# Light_Controller.net
KiCad netlist of a schematic drawn in EAGLE
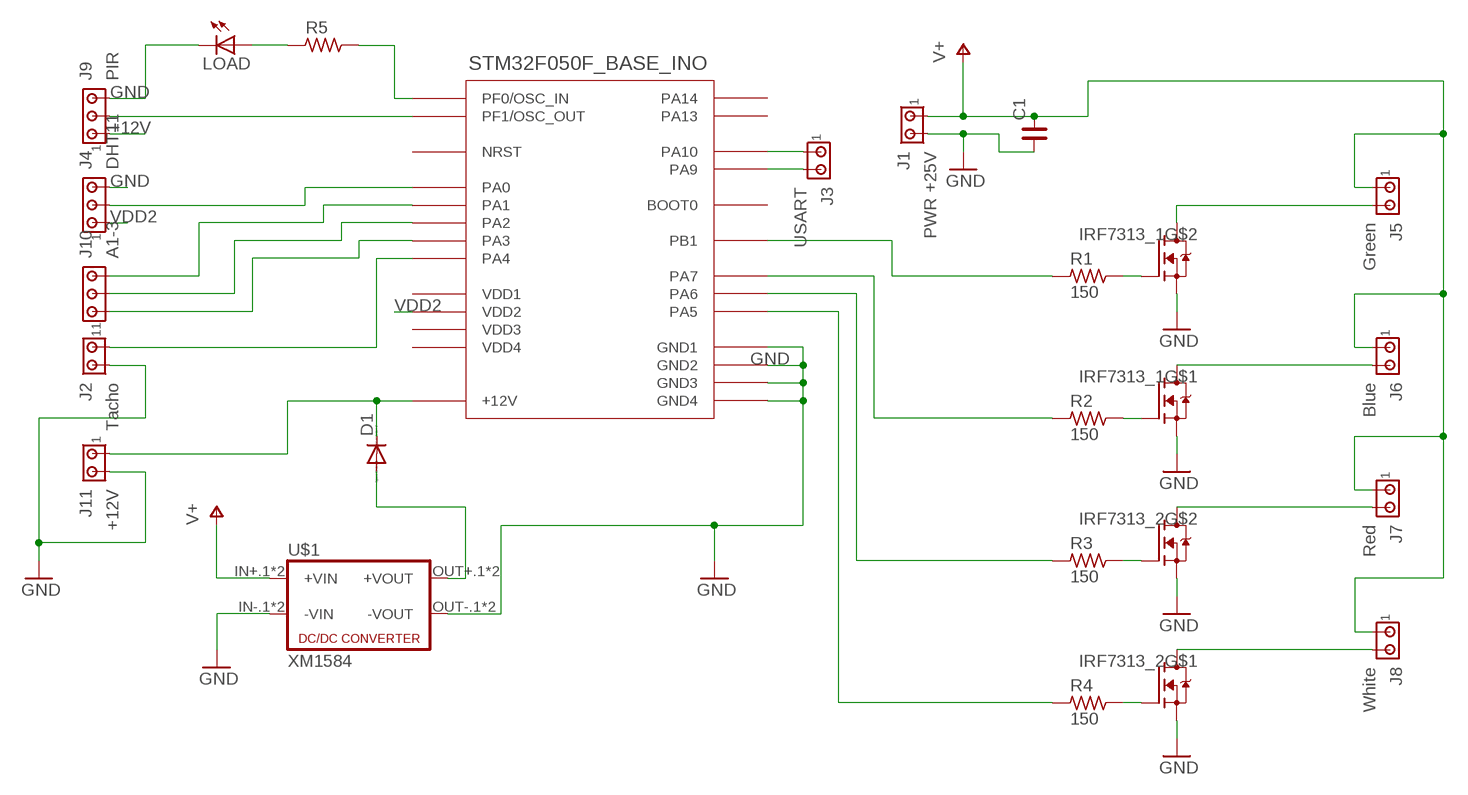
[diagram p0: schematic, sheet 1]

(export (version "E")
  (design (tool "Eeschema 10.0.6"))
  (components
    (comp (ref "C1")
      (value "C_0603")
      (footprint "eagle-import:C0603")
      (libsource (lib "eagle-import") (part "C_0603"))
    )
    (comp (ref "D1")
      (value "DIODE-DO214AC")
      (footprint "eagle-import:DO214AC")
      (libsource (lib "eagle-import") (part "DIODE-DO214AC"))
    )
    (comp (ref "IRF7313_1")
      (value "IRF7313")
      (footprint "eagle-import:SO-8")
      (libsource (lib "eagle-import") (part "IRF7313"))
    )
    (comp (ref "IRF7313_2")
      (value "IRF7313")
      (footprint "eagle-import:SO-8")
      (libsource (lib "eagle-import") (part "IRF7313"))
    )
    (comp (ref "J1")
      (value "PWR +25V")
      (footprint "eagle-import:10X02MTA")
      (libsource (lib "eagle-import") (part "MTA02-100"))
    )
    (comp (ref "J2")
      (value "Tacho")
      (footprint "eagle-import:10X02MTA")
      (libsource (lib "eagle-import") (part "MTA02-100"))
    )
    (comp (ref "J3")
      (value "USART")
      (footprint "eagle-import:10X02MTA")
      (libsource (lib "eagle-import") (part "MTA02-100"))
    )
    (comp (ref "J4")
      (value "DHT11")
      (footprint "eagle-import:10X03MTA")
      (libsource (lib "eagle-import") (part "MTA03-100"))
    )
    (comp (ref "J5")
      (value "Green")
      (footprint "eagle-import:10X02MTA")
      (libsource (lib "eagle-import") (part "MTA02-100"))
    )
    (comp (ref "J6")
      (value "Blue")
      (footprint "eagle-import:10X02MTA")
      (libsource (lib "eagle-import") (part "MTA02-100"))
    )
    (comp (ref "J7")
      (value "Red")
      (footprint "eagle-import:10X02MTA")
      (libsource (lib "eagle-import") (part "MTA02-100"))
    )
    (comp (ref "J8")
      (value "White")
      (footprint "eagle-import:10X02MTA")
      (libsource (lib "eagle-import") (part "MTA02-100"))
    )
    (comp (ref "J9")
      (value "PIR")
      (footprint "eagle-import:10X03MTA")
      (libsource (lib "eagle-import") (part "MTA03-100"))
    )
    (comp (ref "J10")
      (value "A1-3")
      (footprint "eagle-import:10X03MTA")
      (libsource (lib "eagle-import") (part "MTA03-100"))
    )
    (comp (ref "J11")
      (value "+12V")
      (footprint "eagle-import:10X02MTA")
      (libsource (lib "eagle-import") (part "MTA02-100"))
    )
    (comp (ref "LOAD")
      (value "LEDCHIPLED_1206")
      (footprint "eagle-import:CHIPLED_1206")
      (libsource (lib "eagle-import") (part "LEDCHIPLED_1206"))
    )
    (comp (ref "R1")
      (value "150")
      (footprint "eagle-import:R1206")
      (libsource (lib "eagle-import") (part "R_1206"))
    )
    (comp (ref "R2")
      (value "150")
      (footprint "eagle-import:R1206")
      (libsource (lib "eagle-import") (part "R_1206"))
    )
    (comp (ref "R3")
      (value "150")
      (footprint "eagle-import:R1206")
      (libsource (lib "eagle-import") (part "R_1206"))
    )
    (comp (ref "R4")
      (value "150")
      (footprint "eagle-import:R1206")
      (libsource (lib "eagle-import") (part "R_1206"))
    )
    (comp (ref "R5")
      (value "R_1206")
      (footprint "eagle-import:R1206")
      (libsource (lib "eagle-import") (part "R_1206"))
    )
    (comp (ref "STM321")
      (value "STM32F050F_BASE_INO")
      (footprint "eagle-import:STM32_BASE_INO")
      (libsource (lib "eagle-import") (part "STM32F050F_BASE_INO"))
    )
    (comp (ref "U$1")
      (value "XM1584")
      (footprint "eagle-import:XM1584")
      (libsource (lib "eagle-import") (part "XM1584"))
    )
  )
  (nets
    (net (code "1") (name "/+12V") (class "Default")
      (node (ref "D1") (pin "C") (pinfunction "C_C") (pintype "passive"))
      (node (ref "J11") (pin "1") (pinfunction "1_1") (pintype "passive"))
      (node (ref "J9") (pin "1") (pinfunction "1_1") (pintype "passive"))
      (node (ref "STM321") (pin "+12V") (pinfunction "+12V_+12V") (pintype "passive"))
    )
    (net (code "2") (name "/VDD2") (class "Default")
      (node (ref "J4") (pin "1") (pinfunction "1_1") (pintype "passive"))
      (node (ref "STM321") (pin "VDD2") (pinfunction "VDD2_VDD2") (pintype "passive"))
    )
    (net (code "3") (name "GND") (class "Default")
      (node (ref "C1") (pin "1") (pinfunction "1_1") (pintype "passive"))
      (node (ref "IRF7313_1") (pin "1") (pinfunction "S_1") (pintype "passive"))
      (node (ref "IRF7313_1") (pin "3") (pinfunction "S_3") (pintype "passive"))
      (node (ref "IRF7313_2") (pin "1") (pinfunction "S_1") (pintype "passive"))
      (node (ref "IRF7313_2") (pin "3") (pinfunction "S_3") (pintype "passive"))
      (node (ref "J1") (pin "2") (pinfunction "2_2") (pintype "passive"))
      (node (ref "J11") (pin "2") (pinfunction "2_2") (pintype "passive"))
      (node (ref "J2") (pin "2") (pinfunction "2_2") (pintype "passive"))
      (node (ref "J4") (pin "3") (pinfunction "3_3") (pintype "passive"))
      (node (ref "J9") (pin "3") (pinfunction "3_3") (pintype "passive"))
      (node (ref "LOAD") (pin "C") (pinfunction "C_C") (pintype "passive"))
      (node (ref "STM321") (pin "GND1") (pinfunction "GND1_GND1") (pintype "passive"))
      (node (ref "STM321") (pin "GND2") (pinfunction "GND2_GND2") (pintype "passive"))
      (node (ref "STM321") (pin "GND3") (pinfunction "GND3_GND3") (pintype "passive"))
      (node (ref "STM321") (pin "GND4") (pinfunction "GND4_GND4") (pintype "passive"))
      (node (ref "U$1") (pin "IN-.1") (pinfunction "-VIN_IN-.1") (pintype "passive"))
      (node (ref "U$1") (pin "IN-.2") (pinfunction "-VIN_IN-.2") (pintype "passive"))
      (node (ref "U$1") (pin "OUT-.1") (pinfunction "-VOUT_OUT-.1") (pintype "passive"))
      (node (ref "U$1") (pin "OUT-.2") (pinfunction "-VOUT_OUT-.2") (pintype "passive"))
    )
    (net (code "4") (name "Net-(D1-PadA)") (class "Default")
      (node (ref "D1") (pin "A") (pinfunction "A_A") (pintype "passive"))
      (node (ref "U$1") (pin "OUT+.1") (pinfunction "+VOUT_OUT+.1") (pintype "passive"))
      (node (ref "U$1") (pin "OUT+.2") (pinfunction "+VOUT_OUT+.2") (pintype "passive"))
    )
    (net (code "5") (name "Net-(IRF7313_1A-D-Pad7)") (class "Default")
      (node (ref "IRF7313_1") (pin "7") (pinfunction "D_7") (pintype "passive"))
      (node (ref "IRF7313_1") (pin "8") (pinfunction "D_8") (pintype "passive"))
      (node (ref "J6") (pin "2") (pinfunction "2_2") (pintype "passive"))
    )
    (net (code "6") (name "Net-(IRF7313_1A-G)") (class "Default")
      (node (ref "IRF7313_1") (pin "2") (pinfunction "G_2") (pintype "passive"))
      (node (ref "R2") (pin "2") (pinfunction "2_2") (pintype "passive"))
    )
    (net (code "7") (name "Net-(IRF7313_1B-D-Pad5)") (class "Default")
      (node (ref "IRF7313_1") (pin "5") (pinfunction "D_5") (pintype "passive"))
      (node (ref "IRF7313_1") (pin "6") (pinfunction "D_6") (pintype "passive"))
      (node (ref "J5") (pin "2") (pinfunction "2_2") (pintype "passive"))
    )
    (net (code "8") (name "Net-(IRF7313_1B-G)") (class "Default")
      (node (ref "IRF7313_1") (pin "4") (pinfunction "G_4") (pintype "passive"))
      (node (ref "R1") (pin "2") (pinfunction "2_2") (pintype "passive"))
    )
    (net (code "9") (name "Net-(IRF7313_2A-D-Pad7)") (class "Default")
      (node (ref "IRF7313_2") (pin "7") (pinfunction "D_7") (pintype "passive"))
      (node (ref "IRF7313_2") (pin "8") (pinfunction "D_8") (pintype "passive"))
      (node (ref "J8") (pin "2") (pinfunction "2_2") (pintype "passive"))
    )
    (net (code "10") (name "Net-(IRF7313_2A-G)") (class "Default")
      (node (ref "IRF7313_2") (pin "2") (pinfunction "G_2") (pintype "passive"))
      (node (ref "R4") (pin "2") (pinfunction "2_2") (pintype "passive"))
    )
    (net (code "11") (name "Net-(IRF7313_2B-D-Pad5)") (class "Default")
      (node (ref "IRF7313_2") (pin "5") (pinfunction "D_5") (pintype "passive"))
      (node (ref "IRF7313_2") (pin "6") (pinfunction "D_6") (pintype "passive"))
      (node (ref "J7") (pin "2") (pinfunction "2_2") (pintype "passive"))
    )
    (net (code "12") (name "Net-(IRF7313_2B-G)") (class "Default")
      (node (ref "IRF7313_2") (pin "4") (pinfunction "G_4") (pintype "passive"))
      (node (ref "R3") (pin "2") (pinfunction "2_2") (pintype "passive"))
    )
    (net (code "13") (name "Net-(J2-Pad1)") (class "Default")
      (node (ref "J2") (pin "1") (pinfunction "1_1") (pintype "passive"))
      (node (ref "STM321") (pin "PA4") (pinfunction "PA4_PA4") (pintype "passive"))
    )
    (net (code "14") (name "Net-(J3-Pad1)") (class "Default")
      (node (ref "J3") (pin "1") (pinfunction "1_1") (pintype "passive"))
      (node (ref "STM321") (pin "PA10") (pinfunction "PA10_PA10") (pintype "passive"))
    )
    (net (code "15") (name "Net-(J3-Pad2)") (class "Default")
      (node (ref "J3") (pin "2") (pinfunction "2_2") (pintype "passive"))
      (node (ref "STM321") (pin "PA9") (pinfunction "PA9_PA9") (pintype "passive"))
    )
    (net (code "16") (name "Net-(J4-Pad2)") (class "Default")
      (node (ref "J4") (pin "2") (pinfunction "2_2") (pintype "passive"))
      (node (ref "STM321") (pin "PA0") (pinfunction "PA0_PA0") (pintype "passive"))
    )
    (net (code "17") (name "Net-(J10-Pad1)") (class "Default")
      (node (ref "J10") (pin "1") (pinfunction "1_1") (pintype "passive"))
      (node (ref "STM321") (pin "PA3") (pinfunction "PA3_PA3") (pintype "passive"))
    )
    (net (code "18") (name "Net-(J10-Pad2)") (class "Default")
      (node (ref "J10") (pin "2") (pinfunction "2_2") (pintype "passive"))
      (node (ref "STM321") (pin "PA2") (pinfunction "PA2_PA2") (pintype "passive"))
    )
    (net (code "19") (name "Net-(J10-Pad3)") (class "Default")
      (node (ref "J10") (pin "3") (pinfunction "3_3") (pintype "passive"))
      (node (ref "STM321") (pin "PA1") (pinfunction "PA1_PA1") (pintype "passive"))
    )
    (net (code "20") (name "Net-(LOAD-PadA)") (class "Default")
      (node (ref "LOAD") (pin "A") (pinfunction "A_A") (pintype "passive"))
      (node (ref "R5") (pin "1") (pinfunction "1_1") (pintype "passive"))
    )
    (net (code "21") (name "Net-(R1-Pad1)") (class "Default")
      (node (ref "R1") (pin "1") (pinfunction "1_1") (pintype "passive"))
      (node (ref "STM321") (pin "PB1") (pinfunction "PB1_PB1") (pintype "passive"))
    )
    (net (code "22") (name "Net-(R2-Pad1)") (class "Default")
      (node (ref "R2") (pin "1") (pinfunction "1_1") (pintype "passive"))
      (node (ref "STM321") (pin "PA7") (pinfunction "PA7_PA7") (pintype "passive"))
    )
    (net (code "23") (name "Net-(R3-Pad1)") (class "Default")
      (node (ref "R3") (pin "1") (pinfunction "1_1") (pintype "passive"))
      (node (ref "STM321") (pin "PA6") (pinfunction "PA6_PA6") (pintype "passive"))
    )
    (net (code "24") (name "Net-(R4-Pad1)") (class "Default")
      (node (ref "R4") (pin "1") (pinfunction "1_1") (pintype "passive"))
      (node (ref "STM321") (pin "PA5") (pinfunction "PA5_PA5") (pintype "passive"))
    )
    (net (code "25") (name "Net-(STM321-PF0{slash}OSC_IN)") (class "Default")
      (node (ref "R5") (pin "2") (pinfunction "2_2") (pintype "passive"))
      (node (ref "STM321") (pin "PF0") (pinfunction "PF0/OSC_IN_PF0") (pintype "passive"))
    )
    (net (code "26") (name "Net-(STM321-PF1{slash}OSC_OUT)") (class "Default")
      (node (ref "J9") (pin "2") (pinfunction "2_2") (pintype "passive"))
      (node (ref "STM321") (pin "PF1") (pinfunction "PF1/OSC_OUT_PF1") (pintype "passive"))
    )
    (net (code "27") (name "V+") (class "Default")
      (node (ref "C1") (pin "2") (pinfunction "2_2") (pintype "passive"))
      (node (ref "J1") (pin "1") (pinfunction "1_1") (pintype "passive"))
      (node (ref "J5") (pin "1") (pinfunction "1_1") (pintype "passive"))
      (node (ref "J6") (pin "1") (pinfunction "1_1") (pintype "passive"))
      (node (ref "J7") (pin "1") (pinfunction "1_1") (pintype "passive"))
      (node (ref "J8") (pin "1") (pinfunction "1_1") (pintype "passive"))
      (node (ref "U$1") (pin "IN+.1") (pinfunction "+VIN_IN+.1") (pintype "passive"))
      (node (ref "U$1") (pin "IN+.2") (pinfunction "+VIN_IN+.2") (pintype "passive"))
    )
    (net (code "28") (name "unconnected-(STM321-PadBOOT0)") (class "Default")
      (node (ref "STM321") (pin "BOOT0") (pinfunction "BOOT0_BOOT0") (pintype "passive"))
    )
    (net (code "29") (name "unconnected-(STM321-PadNRST)") (class "Default")
      (node (ref "STM321") (pin "NRST") (pinfunction "NRST_NRST") (pintype "passive"))
    )
    (net (code "30") (name "unconnected-(STM321-PadPA13)") (class "Default")
      (node (ref "STM321") (pin "PA13") (pinfunction "PA13_PA13") (pintype "passive"))
    )
    (net (code "31") (name "unconnected-(STM321-PadPA14)") (class "Default")
      (node (ref "STM321") (pin "PA14") (pinfunction "PA14_PA14") (pintype "passive"))
    )
    (net (code "32") (name "unconnected-(STM321-PadVDD1)") (class "Default")
      (node (ref "STM321") (pin "VDD1") (pinfunction "VDD1_VDD1") (pintype "passive"))
    )
    (net (code "33") (name "unconnected-(STM321-PadVDD3)") (class "Default")
      (node (ref "STM321") (pin "VDD3") (pinfunction "VDD3_VDD3") (pintype "passive"))
    )
    (net (code "34") (name "unconnected-(STM321-PadVDD4)") (class "Default")
      (node (ref "STM321") (pin "VDD4") (pinfunction "VDD4_VDD4") (pintype "passive"))
    )
  )
)
